# fan_control.net
KiCad netlist of a schematic drawn in EAGLE
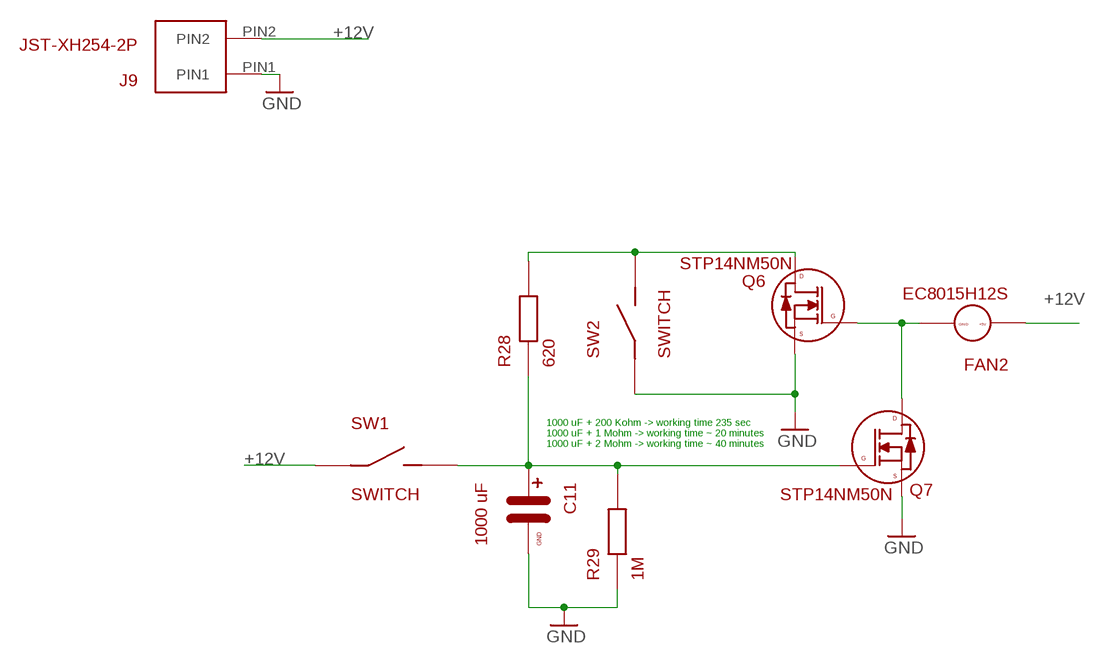
[diagram p0: schematic, sheet 1]

(export (version "E")
  (design (tool "Eeschema 10.0.6"))
  (components
    (comp (ref "C11")
      (value "1000 uF")
      (footprint "eagle-import:C")
      (libsource (lib "eagle-import") (part "C"))
    )
    (comp (ref "FAN2")
      (value "EC8015H12S")
      (footprint "eagle-import:FAN_5V")
      (libsource (lib "eagle-import") (part "FAN_5V"))
    )
    (comp (ref "J9")
      (value "JST-XH254-2P")
      (footprint "eagle-import:JST-XH254-2P")
      (libsource (lib "eagle-import") (part "JST-XH254-2P"))
    )
    (comp (ref "Q6")
      (value "STP14NM50N")
      (footprint "eagle-import:MOSFET_N")
      (fields (field (name "SPICEPREFIX") "Q"))
      (libsource (lib "eagle-import") (part "MOSFET_N"))
    )
    (comp (ref "Q7")
      (value "STP14NM50N")
      (footprint "eagle-import:MOSFET_N")
      (libsource (lib "eagle-import") (part "MOSFET_N"))
    )
    (comp (ref "R28") (value "620") (footprint "eagle-import:R") (libsource (lib "eagle-import") (part "R")))
    (comp (ref "R29") (value "1M") (footprint "eagle-import:R") (libsource (lib "eagle-import") (part "R")))
    (comp (ref "SW1")
      (value "SWITCH")
      (footprint "eagle-import:SWITCH")
      (libsource (lib "eagle-import") (part "SWITCH"))
    )
    (comp (ref "SW2")
      (value "SWITCH")
      (footprint "eagle-import:SWITCH")
      (libsource (lib "eagle-import") (part "SWITCH"))
    )
  )
  (nets
    (net (code "1") (name "/+12V") (class "Default")
      (node (ref "FAN2") (pin "VCC") (pinfunction "VCC_VCC") (pintype "power_in"))
      (node (ref "J9") (pin "PIN2") (pinfunction "PIN2_PIN2") (pintype "bidirectional"))
      (node (ref "SW1") (pin "P$1") (pinfunction "P$1_P$1") (pintype "bidirectional"))
    )
    (net (code "2") (name "GND") (class "Default")
      (node (ref "C11") (pin "PIN_GND") (pinfunction "PIN_GND_PIN_GND") (pintype "bidirectional"))
      (node (ref "J9") (pin "PIN1") (pinfunction "PIN1_PIN1") (pintype "bidirectional"))
      (node (ref "Q6") (pin "S") (pinfunction "S_S") (pintype "bidirectional"))
      (node (ref "Q7") (pin "S") (pinfunction "S_S") (pintype "bidirectional"))
      (node (ref "R29") (pin "P$1") (pinfunction "P$1_P$1") (pintype "bidirectional"))
      (node (ref "SW2") (pin "P$1") (pinfunction "P$1_P$1") (pintype "bidirectional"))
    )
    (net (code "3") (name "Net-(C11-PadPIN_PLUS)") (class "Default")
      (node (ref "C11") (pin "PIN_PLUS") (pinfunction "PIN_PLUS_PIN_PLUS") (pintype "bidirectional"))
      (node (ref "Q7") (pin "G") (pinfunction "G_G") (pintype "bidirectional"))
      (node (ref "R28") (pin "P$1") (pinfunction "P$1_P$1") (pintype "bidirectional"))
      (node (ref "R29") (pin "P$2") (pinfunction "P$2_P$2") (pintype "bidirectional"))
      (node (ref "SW1") (pin "P$2") (pinfunction "P$2_P$2") (pintype "bidirectional"))
    )
    (net (code "4") (name "Net-(FAN2-PadGND)") (class "Default")
      (node (ref "FAN2") (pin "GND") (pinfunction "GND_GND") (pintype "power_in"))
      (node (ref "Q6") (pin "G") (pinfunction "G_G") (pintype "bidirectional"))
      (node (ref "Q7") (pin "D") (pinfunction "D_D") (pintype "bidirectional"))
    )
    (net (code "5") (name "Net-(Q6-PadD)") (class "Default")
      (node (ref "Q6") (pin "D") (pinfunction "D_D") (pintype "bidirectional"))
      (node (ref "R28") (pin "P$2") (pinfunction "P$2_P$2") (pintype "bidirectional"))
      (node (ref "SW2") (pin "P$2") (pinfunction "P$2_P$2") (pintype "bidirectional"))
    )
  )
)
